# xuefei-lab7.net
KiCad netlist of a schematic drawn in EAGLE
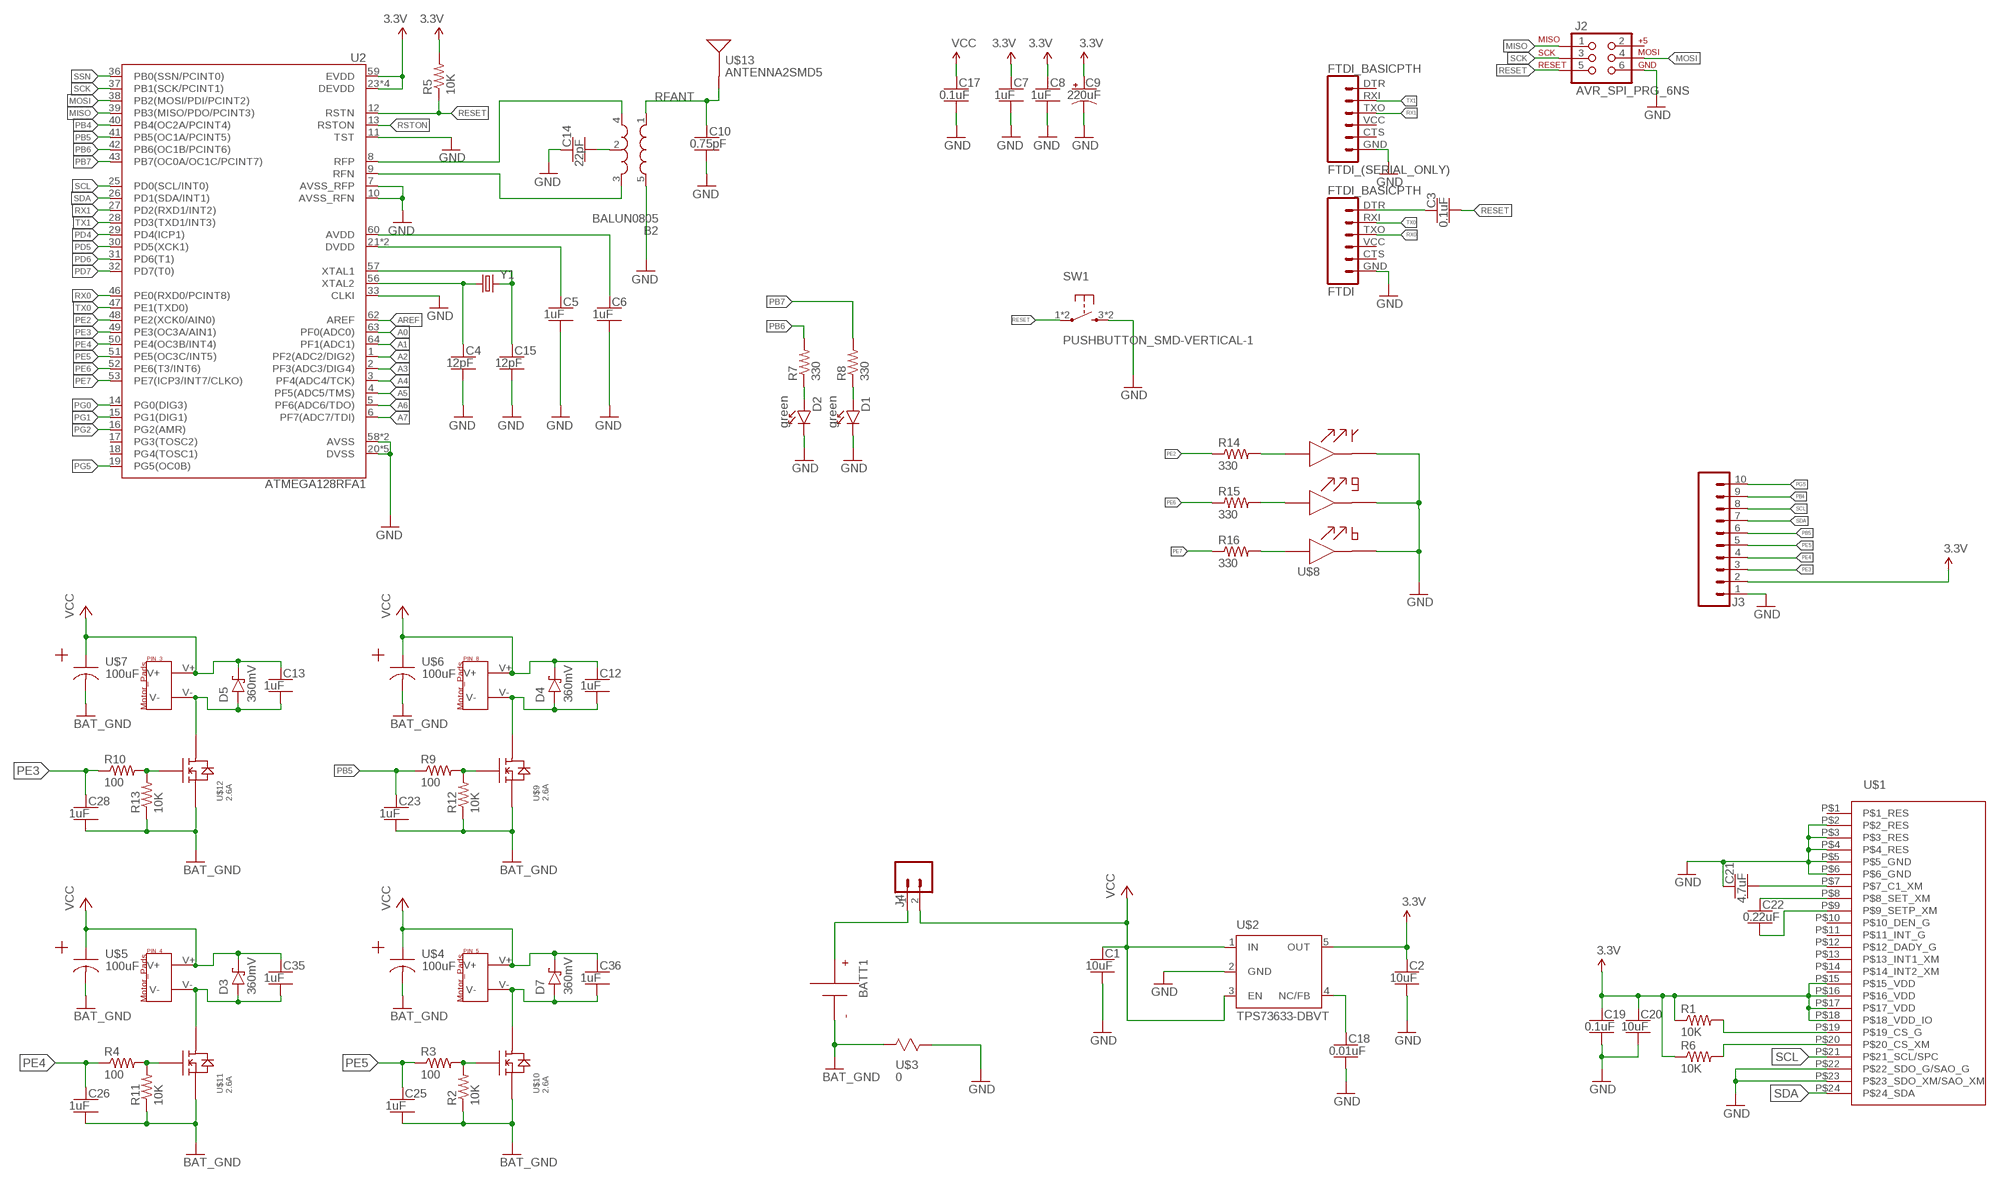
[diagram p0: schematic, sheet 1]

(export (version "E")
  (design (tool "Eeschema 10.0.6"))
  (components
    (comp (ref "B2")
      (value "BALUN0805")
      (footprint "eagle-import:BALUN")
      (fields (field (name "MFR") "Wurth Electronics Inc") (field (name "MPN") "748421245"))
      (libsource (lib "eagle-import") (part "BALUN0805"))
    )
    (comp (ref "BATT1")
      (value "BATTERY-HUBSAN-W/HOLDER")
      (footprint "eagle-import:BATTERY-W_HOLDER-380MAH-HUBSAN")
      (fields
        (field (name "MFR") "HUBSAN")
        (field (name "MPN") "X4-H107C-8-in-1")
        (field (name "CREATOR") "Swanson")
      )
      (libsource (lib "eagle-import") (part "BATTERY-HUBSAN-W/HOLDER"))
    )
    (comp (ref "C1")
      (value "10uF")
      (footprint "eagle-import:CAPC2012X140_HS")
      (fields
        (field (name "MFR") "Murata Electronics North America")
        (field (name "MPN") "GRM21BR61E106KA73L")
      )
      (libsource (lib "eagle-import") (part "CAPACITOR-NP_SMD-2012-0805_CERAMIC-10UF"))
    )
    (comp (ref "C2")
      (value "10uF")
      (footprint "eagle-import:CAPC2012X140_HS")
      (fields
        (field (name "MFR") "Murata Electronics North America")
        (field (name "MPN") "GRM21BR61E106KA73L")
      )
      (libsource (lib "eagle-import") (part "CAPACITOR-NP_SMD-2012-0805_CERAMIC-10UF"))
    )
    (comp (ref "C3")
      (value "0.1uF")
      (footprint "eagle-import:CAPC2012X140_HS")
      (fields
        (field (name "MFR") "Murata Electronics North America")
        (field (name "MPN") "GRM21BR71H104KA01L")
      )
      (libsource (lib "eagle-import") (part "CAPACITOR-NP_SMD-2012-0805_CERAMIC-0.1UF"))
    )
    (comp (ref "C4")
      (value "12pF")
      (footprint "eagle-import:CAPC2012X140_HS")
      (fields
        (field (name "MFR") "Murata Electronics North America")
        (field (name "MPN") "GRM21A5C2E120JW01D")
      )
      (libsource (lib "eagle-import") (part "CAPACITOR-NP_SMD-2012-0805_CERAMIC-12PF"))
    )
    (comp (ref "C5")
      (value "1uF")
      (footprint "eagle-import:CAPC2012X140_HS")
      (fields
        (field (name "MFR") "Murata Electronics North America")
        (field (name "MPN") "GRM21BR71H105KA12L")
      )
      (libsource (lib "eagle-import") (part "CAPACITOR-NP_SMD-2012-0805_CERAMIC-1UF"))
    )
    (comp (ref "C6")
      (value "1uF")
      (footprint "eagle-import:CAPC2012X140_HS")
      (fields
        (field (name "MFR") "Murata Electronics North America")
        (field (name "MPN") "GRM21BR71H105KA12L")
      )
      (libsource (lib "eagle-import") (part "CAPACITOR-NP_SMD-2012-0805_CERAMIC-1UF"))
    )
    (comp (ref "C7")
      (value "1uF")
      (footprint "eagle-import:CAPC2012X140_HS")
      (fields
        (field (name "MFR") "Murata Electronics North America")
        (field (name "MPN") "GRM21BR71H105KA12L")
      )
      (libsource (lib "eagle-import") (part "CAPACITOR-NP_SMD-2012-0805_CERAMIC-1UF"))
    )
    (comp (ref "C8")
      (value "1uF")
      (footprint "eagle-import:CAPC2012X140_HS")
      (fields
        (field (name "MFR") "Murata Electronics North America")
        (field (name "MPN") "GRM21BR71H105KA12L")
      )
      (libsource (lib "eagle-import") (part "CAPACITOR-NP_SMD-2012-0805_CERAMIC-1UF"))
    )
    (comp (ref "C9")
      (value "220uF")
      (footprint "eagle-import:CAPMP7343X310_HS")
      (fields (field (name "MFR") "AVX Corporation") (field (name "MPN") "TAJD227K006RNJ"))
      (libsource (lib "eagle-import") (part "CAPACITOR-POL_SMD-7043-D_TANTALUM-220UF"))
    )
    (comp (ref "C10")
      (value "0.75pF")
      (footprint "eagle-import:CAPC2012X140_HS")
      (fields
        (field (name "MFR") "Murata Electronics North America")
        (field (name "MPN") "GQM2195C2AR75CB01D")
      )
      (libsource (lib "eagle-import") (part "CAPACITOR-NP_SMD-2012-0805_CERAMIC-0.75PF"))
    )
    (comp (ref "C12")
      (value "1uF")
      (footprint "eagle-import:CAPC2012X140_HS")
      (fields
        (field (name "MFR") "Murata Electronics North America")
        (field (name "MPN") "GRM21BR71H105KA12L")
      )
      (libsource (lib "eagle-import") (part "CAPACITOR-NP_SMD-2012-0805_CERAMIC-1UF"))
    )
    (comp (ref "C13")
      (value "1uF")
      (footprint "eagle-import:CAPC2012X140_HS")
      (fields
        (field (name "MFR") "Murata Electronics North America")
        (field (name "MPN") "GRM21BR71H105KA12L")
      )
      (libsource (lib "eagle-import") (part "CAPACITOR-NP_SMD-2012-0805_CERAMIC-1UF"))
    )
    (comp (ref "C14")
      (value "22pF")
      (footprint "eagle-import:CAPC2012X140_HS")
      (fields
        (field (name "MFR") "Murata Electronics North America")
        (field (name "MPN") "GRM21A5C2E220JW01D")
      )
      (libsource (lib "eagle-import") (part "CAPACITOR-NP_SMD-2012-0805_CERAMIC-22PF"))
    )
    (comp (ref "C15")
      (value "12pF")
      (footprint "eagle-import:CAPC2012X140_HS")
      (fields
        (field (name "MFR") "Murata Electronics North America")
        (field (name "MPN") "GRM21A5C2E120JW01D")
      )
      (libsource (lib "eagle-import") (part "CAPACITOR-NP_SMD-2012-0805_CERAMIC-12PF"))
    )
    (comp (ref "C17")
      (value "0.1uF")
      (footprint "eagle-import:CAPC2012X140_HS")
      (fields
        (field (name "MFR") "Murata Electronics North America")
        (field (name "MPN") "GRM21BR71H104KA01L")
      )
      (libsource (lib "eagle-import") (part "CAPACITOR-NP_SMD-2012-0805_CERAMIC-0.1UF"))
    )
    (comp (ref "C18")
      (value "0.01uF")
      (footprint "eagle-import:CAPC2012X140_HS")
      (fields
        (field (name "MFR") "Murata Electronics North America")
        (field (name "MPN") "GRM2195C1H103FA01D")
      )
      (libsource (lib "eagle-import") (part "CAPACITOR-NP_SMD-2012-0805_CERAMIC-0.01UF"))
    )
    (comp (ref "C19")
      (value "0.1uF")
      (footprint "eagle-import:CAPC2012X140_HS")
      (fields
        (field (name "MFR") "Murata Electronics North America")
        (field (name "MPN") "GRM21BR71H104KA01L")
      )
      (libsource (lib "eagle-import") (part "CAPACITOR-NP_SMD-2012-0805_CERAMIC-0.1UF"))
    )
    (comp (ref "C20")
      (value "10uF")
      (footprint "eagle-import:CAPC2012X140_HS")
      (fields
        (field (name "MFR") "Murata Electronics North America")
        (field (name "MPN") "GRM21BR61E106KA73L")
      )
      (libsource (lib "eagle-import") (part "CAPACITOR-NP_SMD-2012-0805_CERAMIC-10UF"))
    )
    (comp (ref "C21")
      (value "4.7uF")
      (footprint "eagle-import:CAPC2012X140_HS")
      (fields
        (field (name "MFR") "Murata Electronics North America")
        (field (name "MPN") "GRM21BR61E475KA12L")
      )
      (libsource (lib "eagle-import") (part "CAPACITOR-NP_SMD-2012-0805_CERAMIC-4.7UF"))
    )
    (comp (ref "C22")
      (value "0.22uF")
      (footprint "eagle-import:CAPC2012X140_HS")
      (fields
        (field (name "MFR") "Murata Electronics North America")
        (field (name "MPN") "GRM21BR71H224KA01L")
      )
      (libsource (lib "eagle-import") (part "CAPACITOR-NP_SMD-2012-0805_CERAMIC-0.22UF"))
    )
    (comp (ref "C23")
      (value "1uF")
      (footprint "eagle-import:CAPC2012X140_HS")
      (fields
        (field (name "MFR") "Murata Electronics North America")
        (field (name "MPN") "GRM21BR71H105KA12L")
      )
      (libsource (lib "eagle-import") (part "CAPACITOR-NP_SMD-2012-0805_CERAMIC-1UF"))
    )
    (comp (ref "C25")
      (value "1uF")
      (footprint "eagle-import:CAPC2012X140_HS")
      (fields
        (field (name "MFR") "Murata Electronics North America")
        (field (name "MPN") "GRM21BR71H105KA12L")
      )
      (libsource (lib "eagle-import") (part "CAPACITOR-NP_SMD-2012-0805_CERAMIC-1UF"))
    )
    (comp (ref "C26")
      (value "1uF")
      (footprint "eagle-import:CAPC2012X140_HS")
      (fields
        (field (name "MFR") "Murata Electronics North America")
        (field (name "MPN") "GRM21BR71H105KA12L")
      )
      (libsource (lib "eagle-import") (part "CAPACITOR-NP_SMD-2012-0805_CERAMIC-1UF"))
    )
    (comp (ref "C28")
      (value "1uF")
      (footprint "eagle-import:CAPC2012X140_HS")
      (fields
        (field (name "MFR") "Murata Electronics North America")
        (field (name "MPN") "GRM21BR71H105KA12L")
      )
      (libsource (lib "eagle-import") (part "CAPACITOR-NP_SMD-2012-0805_CERAMIC-1UF"))
    )
    (comp (ref "C35")
      (value "1uF")
      (footprint "eagle-import:CAPC2012X140_HS")
      (fields
        (field (name "MFR") "Murata Electronics North America")
        (field (name "MPN") "GRM21BR71H105KA12L")
      )
      (libsource (lib "eagle-import") (part "CAPACITOR-NP_SMD-2012-0805_CERAMIC-1UF"))
    )
    (comp (ref "C36")
      (value "1uF")
      (footprint "eagle-import:CAPC2012X140_HS")
      (fields
        (field (name "MFR") "Murata Electronics North America")
        (field (name "MPN") "GRM21BR71H105KA12L")
      )
      (libsource (lib "eagle-import") (part "CAPACITOR-NP_SMD-2012-0805_CERAMIC-1UF"))
    )
    (comp (ref "D1")
      (value "green")
      (footprint "eagle-import:LEDSC125X200X120-2_HS")
      (fields (field (name "MFR") "Lite-On Inc") (field (name "MPN") "LTST-C170GKT"))
      (libsource (lib "eagle-import") (part "DIODE-LED_SMD-2012-0805-GREEN"))
    )
    (comp (ref "D2")
      (value "green")
      (footprint "eagle-import:LEDSC125X200X120-2_HS")
      (fields (field (name "MFR") "Lite-On Inc") (field (name "MPN") "LTST-C170GKT"))
      (libsource (lib "eagle-import") (part "DIODE-LED_SMD-2012-0805-GREEN"))
    )
    (comp (ref "D3")
      (value "360mV")
      (footprint "eagle-import:SOD3716X135_HS")
      (fields
        (field (name "MFR") "Toshiba Semiconductor and Storage")
        (field (name "MPN") "CRS08(TE85L,Q,M)")
      )
      (libsource (lib "eagle-import") (part "DIODE-SCHOTTKY_SMD-SOD123-360MV"))
    )
    (comp (ref "D4")
      (value "360mV")
      (footprint "eagle-import:SOD3716X135_HS")
      (fields
        (field (name "MFR") "Toshiba Semiconductor and Storage")
        (field (name "MPN") "CRS08(TE85L,Q,M)")
      )
      (libsource (lib "eagle-import") (part "DIODE-SCHOTTKY_SMD-SOD123-360MV"))
    )
    (comp (ref "D5")
      (value "360mV")
      (footprint "eagle-import:SOD3716X135_HS")
      (fields
        (field (name "MFR") "Toshiba Semiconductor and Storage")
        (field (name "MPN") "CRS08(TE85L,Q,M)")
      )
      (libsource (lib "eagle-import") (part "DIODE-SCHOTTKY_SMD-SOD123-360MV"))
    )
    (comp (ref "D7")
      (value "360mV")
      (footprint "eagle-import:SOD3716X135_HS")
      (fields
        (field (name "MFR") "Toshiba Semiconductor and Storage")
        (field (name "MPN") "CRS08(TE85L,Q,M)")
      )
      (libsource (lib "eagle-import") (part "DIODE-SCHOTTKY_SMD-SOD123-360MV"))
    )
    (comp (ref "FTDI")
      (value "FTDI_BASICPTH")
      (footprint "eagle-import:FTDI_BASIC")
      (fields (field (name "MFR") "Amphenol FCI") (field (name "MPN") "68016-406HLF"))
      (libsource (lib "eagle-import") (part "FTDI_BASICPTH"))
    )
    (comp (ref "FTDI_(SERIAL_ONLY)")
      (value "FTDI_BASICPTH")
      (footprint "eagle-import:FTDI_BASIC")
      (fields (field (name "MFR") "Amphenol FCI") (field (name "MPN") "68016-406HLF"))
      (libsource (lib "eagle-import") (part "FTDI_BASICPTH"))
    )
    (comp (ref "J2")
      (value "AVR_SPI_PRG_6NS")
      (footprint "eagle-import:2X3-NS")
      (fields (field (name "MFR") "Amphenol FCI") (field (name "MPN") "67997-206HLF"))
      (libsource (lib "eagle-import") (part "AVR_SPI_PRG_6NS"))
    )
    (comp (ref "J3")
      (value "SIP-10_TH-254X10-1")
      (footprint "eagle-import:HDRV10W63P254_10X1_2540X254H838_HS")
      (fields (field (name "MFR") "Amphenol FCI") (field (name "MPN") "68000-110HLF"))
      (libsource (lib "eagle-import") (part "SIP-10_TH-254X10-1"))
    )
    (comp (ref "J4")
      (value "MALE_HEADER_2POS-2X1-0.1IN")
      (footprint "eagle-import:MALE_HEADER_2X1_0.1IN")
      (fields
        (field (name "MFR") "3M")
        (field (name "MPN") "961102-6404-AR")
        (field (name "CREATOR") "SWANSON")
      )
      (libsource (lib "eagle-import") (part "MALE_HEADER_2POS-2X1-0.1IN"))
    )
    (comp (ref "PIN_3")
      (value "MOTOR_PADS")
      (footprint "eagle-import:MOTOR_PADS")
      (fields (field (name "MFR") "NA"))
      (libsource (lib "eagle-import") (part "MOTOR_PADS"))
    )
    (comp (ref "PIN_4")
      (value "MOTOR_PADS")
      (footprint "eagle-import:MOTOR_PADS")
      (fields (field (name "MFR") "NA"))
      (libsource (lib "eagle-import") (part "MOTOR_PADS"))
    )
    (comp (ref "PIN_5")
      (value "MOTOR_PADS")
      (footprint "eagle-import:MOTOR_PADS")
      (fields (field (name "MFR") "NA"))
      (libsource (lib "eagle-import") (part "MOTOR_PADS"))
    )
    (comp (ref "PIN_8")
      (value "MOTOR_PADS")
      (footprint "eagle-import:MOTOR_PADS")
      (fields (field (name "MFR") "NA"))
      (libsource (lib "eagle-import") (part "MOTOR_PADS"))
    )
    (comp (ref "R1")
      (value "10K")
      (footprint "eagle-import:RESC2012X60_HS")
      (fields (field (name "MFR") "Yageo") (field (name "MPN") "RC0805JR-0710KL"))
      (libsource (lib "eagle-import") (part "RESISTOR_SMD-2012-0805-10K"))
    )
    (comp (ref "R2")
      (value "10K")
      (footprint "eagle-import:RESC2012X60_HS")
      (fields (field (name "MFR") "Yageo") (field (name "MPN") "RC0805JR-0710KL"))
      (libsource (lib "eagle-import") (part "RESISTOR_SMD-2012-0805-10K"))
    )
    (comp (ref "R3")
      (value "100")
      (footprint "eagle-import:RESC2012X60_HS")
      (fields (field (name "MFR") "Yageo") (field (name "MPN") "RC0805JR-07100RL"))
      (libsource (lib "eagle-import") (part "RESISTOR_SMD-2012-0805-100"))
    )
    (comp (ref "R4")
      (value "100")
      (footprint "eagle-import:RESC2012X60_HS")
      (fields (field (name "MFR") "Yageo") (field (name "MPN") "RC0805JR-07100RL"))
      (libsource (lib "eagle-import") (part "RESISTOR_SMD-2012-0805-100"))
    )
    (comp (ref "R5")
      (value "10K")
      (footprint "eagle-import:RESC2012X60_HS")
      (fields (field (name "MFR") "Yageo") (field (name "MPN") "RC0805JR-0710KL"))
      (libsource (lib "eagle-import") (part "RESISTOR_SMD-2012-0805-10K"))
    )
    (comp (ref "R6")
      (value "10K")
      (footprint "eagle-import:RESC2012X60_HS")
      (fields (field (name "MFR") "Yageo") (field (name "MPN") "RC0805JR-0710KL"))
      (libsource (lib "eagle-import") (part "RESISTOR_SMD-2012-0805-10K"))
    )
    (comp (ref "R7")
      (value "330")
      (footprint "eagle-import:RESC2012X60_HS")
      (fields (field (name "MFR") "Yageo") (field (name "MPN") "RC0805JR-07330RL"))
      (libsource (lib "eagle-import") (part "RESISTOR_SMD-2012-0805-330"))
    )
    (comp (ref "R8")
      (value "330")
      (footprint "eagle-import:RESC2012X60_HS")
      (fields (field (name "MFR") "Yageo") (field (name "MPN") "RC0805JR-07330RL"))
      (libsource (lib "eagle-import") (part "RESISTOR_SMD-2012-0805-330"))
    )
    (comp (ref "R9")
      (value "100")
      (footprint "eagle-import:RESC2012X60_HS")
      (fields (field (name "MFR") "Yageo") (field (name "MPN") "RC0805JR-07100RL"))
      (libsource (lib "eagle-import") (part "RESISTOR_SMD-2012-0805-100"))
    )
    (comp (ref "R10")
      (value "100")
      (footprint "eagle-import:RESC2012X60_HS")
      (fields (field (name "MFR") "Yageo") (field (name "MPN") "RC0805JR-07100RL"))
      (libsource (lib "eagle-import") (part "RESISTOR_SMD-2012-0805-100"))
    )
    (comp (ref "R11")
      (value "10K")
      (footprint "eagle-import:RESC2012X60_HS")
      (fields (field (name "MFR") "Yageo") (field (name "MPN") "RC0805JR-0710KL"))
      (libsource (lib "eagle-import") (part "RESISTOR_SMD-2012-0805-10K"))
    )
    (comp (ref "R12")
      (value "10K")
      (footprint "eagle-import:RESC2012X60_HS")
      (fields (field (name "MFR") "Yageo") (field (name "MPN") "RC0805JR-0710KL"))
      (libsource (lib "eagle-import") (part "RESISTOR_SMD-2012-0805-10K"))
    )
    (comp (ref "R13")
      (value "10K")
      (footprint "eagle-import:RESC2012X60_HS")
      (fields (field (name "MFR") "Yageo") (field (name "MPN") "RC0805JR-0710KL"))
      (libsource (lib "eagle-import") (part "RESISTOR_SMD-2012-0805-10K"))
    )
    (comp (ref "R14")
      (value "330")
      (footprint "eagle-import:RESC2012X60_HS")
      (fields (field (name "MFR") "Yageo") (field (name "MPN") "RC0805JR-07330RL"))
      (libsource (lib "eagle-import") (part "RESISTOR_SMD-2012-0805-330"))
    )
    (comp (ref "R15")
      (value "330")
      (footprint "eagle-import:RESC2012X60_HS")
      (fields (field (name "MFR") "Yageo") (field (name "MPN") "RC0805JR-07330RL"))
      (libsource (lib "eagle-import") (part "RESISTOR_SMD-2012-0805-330"))
    )
    (comp (ref "R16")
      (value "330")
      (footprint "eagle-import:RESC2012X60_HS")
      (fields (field (name "MFR") "Yageo") (field (name "MPN") "RC0805JR-07330RL"))
      (libsource (lib "eagle-import") (part "RESISTOR_SMD-2012-0805-330"))
    )
    (comp (ref "SW1")
      (value "PUSHBUTTON_SMD-VERTICAL-1")
      (footprint "eagle-import:TE_FSM8JSMA_HS")
      (fields (field (name "MFR") "TE Connectivity Alcoswitch Switches") (field (name "MPN") "FSM4JSMA"))
      (libsource (lib "eagle-import") (part "PUSHBUTTON_SMD-VERTICAL-1"))
    )
    (comp (ref "U$1")
      (value "IMU")
      (footprint "eagle-import:LGA-24_4X4MM")
      (fields
        (field (name "MFR") "STMicroelectronics")
        (field (name "MPN") "LSM9DS0TR")
        (field (name "CREATOR") "Xuefei")
      )
      (libsource (lib "eagle-import") (part "IMU"))
    )
    (comp (ref "U$2")
      (value "TPS73633-DBVT")
      (footprint "eagle-import:SOT23-DBV")
      (fields (field (name "MFR") "Texas Instruments") (field (name "MPN") "LP3985IM5X-3.0/NOPB"))
      (libsource (lib "eagle-import") (part "TPS73633-DBVT"))
    )
    (comp (ref "U$3")
      (value "0")
      (footprint "eagle-import:SMD_RESISTOR")
      (fields
        (field (name "MFR") "Yageo")
        (field (name "MPN") "RC0805JR-070RL")
        (field (name "CREATOR") "Xuefei")
      )
      (libsource (lib "eagle-import") (part "RESISTOR"))
    )
    (comp (ref "U$4")
      (value "100uF")
      (footprint "eagle-import:TAJB_SMB_POLAR_CAP")
      (fields
        (field (name "MFR") "AVX Corporation")
        (field (name "MPN") "TAJB107K006RNJ")
        (field (name "CREATOR") "Xuefei")
      )
      (libsource (lib "eagle-import") (part "POLAR_CAP"))
    )
    (comp (ref "U$5")
      (value "100uF")
      (footprint "eagle-import:TAJB_SMB_POLAR_CAP")
      (fields
        (field (name "MFR") "AVX Corporation")
        (field (name "MPN") "TAJB107K006RNJ")
        (field (name "CREATOR") "Xuefei")
      )
      (libsource (lib "eagle-import") (part "POLAR_CAP"))
    )
    (comp (ref "U$6")
      (value "100uF")
      (footprint "eagle-import:TAJB_SMB_POLAR_CAP")
      (fields
        (field (name "MFR") "AVX Corporation")
        (field (name "MPN") "TAJB107K006RNJ")
        (field (name "CREATOR") "Xuefei")
      )
      (libsource (lib "eagle-import") (part "POLAR_CAP"))
    )
    (comp (ref "U$7")
      (value "100uF")
      (footprint "eagle-import:TAJB_SMB_POLAR_CAP")
      (fields
        (field (name "MFR") "AVX Corporation")
        (field (name "MPN") "TAJB107K006RNJ")
        (field (name "CREATOR") "Xuefei")
      )
      (libsource (lib "eagle-import") (part "POLAR_CAP"))
    )
    (comp (ref "U$8")
      (value "QBLP679E-RGB")
      (footprint "eagle-import:QBLP679E-RGB")
      (fields (field (name "MFR") "QT Brightek (QTB)") (field (name "CREATOR") "Xuefei"))
      (libsource (lib "eagle-import") (part "QBLP679E-RGB"))
    )
    (comp (ref "U$9")
      (value "2.6A")
      (footprint "eagle-import:LITTLE_FOOT_MOSFET_W__HEAT_SPREADER")
      (fields
        (field (name "MFR") "Vishay Siliconix")
        (field (name "MPN") "SI2302CDS-T1-E3")
        (field (name "CREATOR") "Xuefei")
      )
      (libsource (lib "eagle-import") (part "N-CHANNEL_MOSFETW/_HEAT_SINK"))
    )
    (comp (ref "U$10")
      (value "2.6A")
      (footprint "eagle-import:LITTLE_FOOT_MOSFET_W__HEAT_SPREADER")
      (fields
        (field (name "MFR") "Vishay Siliconix")
        (field (name "MPN") "SI2302CDS-T1-E3")
        (field (name "CREATOR") "Xuefei")
      )
      (libsource (lib "eagle-import") (part "N-CHANNEL_MOSFETW/_HEAT_SINK"))
    )
    (comp (ref "U$11")
      (value "2.6A")
      (footprint "eagle-import:LITTLE_FOOT_MOSFET_W__HEAT_SPREADER")
      (fields
        (field (name "MFR") "Vishay Siliconix")
        (field (name "MPN") "SI2302CDS-T1-E3")
        (field (name "CREATOR") "Xuefei")
      )
      (libsource (lib "eagle-import") (part "N-CHANNEL_MOSFETW/_HEAT_SINK"))
    )
    (comp (ref "U$12")
      (value "2.6A")
      (footprint "eagle-import:LITTLE_FOOT_MOSFET_W__HEAT_SPREADER")
      (fields
        (field (name "MFR") "Vishay Siliconix")
        (field (name "MPN") "SI2302CDS-T1-E3")
        (field (name "CREATOR") "Xuefei")
      )
      (libsource (lib "eagle-import") (part "N-CHANNEL_MOSFETW/_HEAT_SINK"))
    )
    (comp (ref "U$13")
      (value "ANTENNA2SMD5")
      (footprint "eagle-import:ANTENNA-CHIP5")
      (fields (field (name "MFR") "Linx Technologies Inc.") (field (name "MPN") "ANT-2.45-CHP-T"))
      (libsource (lib "eagle-import") (part "ANTENNA2SMD5"))
    )
    (comp (ref "U2")
      (value "ATMEGA128RFA1")
      (footprint "eagle-import:QFN-64")
      (fields (field (name "MFR") "Atmel") (field (name "MPN") "ATMEGA128RFA1-ZUR00"))
      (libsource (lib "eagle-import") (part "ATMEGA128RFA1"))
    )
    (comp (ref "Y1")
      (value "CRYSTAL5X3")
      (footprint "eagle-import:CRYSTAL-SMD-5X3")
      (fields (field (name "MFR") "Abracon LLC") (field (name "MPN") "ABM3B-16.000MHZ-B2-T"))
      (libsource (lib "eagle-import") (part "CRYSTAL5X3"))
    )
  )
  (nets
    (net (code "1") (name "/RFANT") (class "Default")
      (node (ref "B2") (pin "1") (pinfunction "IN_1") (pintype "bidirectional"))
      (node (ref "C10") (pin "1") (pinfunction "1_1") (pintype "passive"))
      (node (ref "U$13") (pin "FEED") (pinfunction "SIGNAL_FEED") (pintype "bidirectional"))
    )
    (net (code "2") (name "3.3V") (class "Default")
      (node (ref "C19") (pin "1") (pinfunction "1_1") (pintype "passive"))
      (node (ref "C2") (pin "1") (pinfunction "1_1") (pintype "passive"))
      (node (ref "C20") (pin "1") (pinfunction "1_1") (pintype "passive"))
      (node (ref "C7") (pin "1") (pinfunction "1_1") (pintype "passive"))
      (node (ref "C8") (pin "1") (pinfunction "1_1") (pintype "passive"))
      (node (ref "C9") (pin "1") (pinfunction "+_1") (pintype "passive"))
      (node (ref "J3") (pin "2") (pinfunction "2_2") (pintype "passive"))
      (node (ref "R1") (pin "1") (pinfunction "1_1") (pintype "passive"))
      (node (ref "R5") (pin "2") (pinfunction "2_2") (pintype "passive"))
      (node (ref "R6") (pin "1") (pinfunction "1_1") (pintype "passive"))
      (node (ref "U$1") (pin "P$15") (pinfunction "P$15_VDD_P$15") (pintype "bidirectional"))
      (node (ref "U$1") (pin "P$16") (pinfunction "P$16_VDD_P$16") (pintype "bidirectional"))
      (node (ref "U$1") (pin "P$17") (pinfunction "P$17_VDD_P$17") (pintype "bidirectional"))
      (node (ref "U$1") (pin "P$18") (pinfunction "P$18_VDD_IO_P$18") (pintype "bidirectional"))
      (node (ref "U$2") (pin "5") (pinfunction "OUT_5") (pintype "passive"))
      (node (ref "U2") (pin "23") (pinfunction "DEVDD_23") (pintype "bidirectional"))
      (node (ref "U2") (pin "34") (pinfunction "DEVDD_34") (pintype "bidirectional"))
      (node (ref "U2") (pin "44") (pinfunction "DEVDD_44") (pintype "bidirectional"))
      (node (ref "U2") (pin "54") (pinfunction "DEVDD_54") (pintype "bidirectional"))
      (node (ref "U2") (pin "59") (pinfunction "EVDD_59") (pintype "bidirectional"))
    )
    (net (code "3") (name "A0") (class "Default")
      (node (ref "U2") (pin "63") (pinfunction "PF0(ADC0)_63") (pintype "bidirectional"))
    )
    (net (code "4") (name "A1") (class "Default")
      (node (ref "U2") (pin "64") (pinfunction "PF1(ADC1)_64") (pintype "bidirectional"))
    )
    (net (code "5") (name "A2") (class "Default")
      (node (ref "U2") (pin "1") (pinfunction "PF2(ADC2/DIG2)_1") (pintype "bidirectional"))
    )
    (net (code "6") (name "A3") (class "Default")
      (node (ref "U2") (pin "2") (pinfunction "PF3(ADC3/DIG4)_2") (pintype "bidirectional"))
    )
    (net (code "7") (name "A4") (class "Default")
      (node (ref "U2") (pin "3") (pinfunction "PF4(ADC4/TCK)_3") (pintype "bidirectional"))
    )
    (net (code "8") (name "A5") (class "Default")
      (node (ref "U2") (pin "4") (pinfunction "PF5(ADC5/TMS)_4") (pintype "bidirectional"))
    )
    (net (code "9") (name "A6") (class "Default")
      (node (ref "U2") (pin "5") (pinfunction "PF6(ADC6/TDO)_5") (pintype "bidirectional"))
    )
    (net (code "10") (name "A7") (class "Default")
      (node (ref "U2") (pin "6") (pinfunction "PF7(ADC7/TDI)_6") (pintype "bidirectional"))
    )
    (net (code "11") (name "AREF") (class "Default")
      (node (ref "U2") (pin "62") (pinfunction "AREF_62") (pintype "bidirectional"))
    )
    (net (code "12") (name "BAT_GND") (class "Default")
      (node (ref "BATT1") (pin "-") (pinfunction "N_-") (pintype "bidirectional"))
      (node (ref "C23") (pin "2") (pinfunction "2_2") (pintype "passive"))
      (node (ref "C25") (pin "2") (pinfunction "2_2") (pintype "passive"))
      (node (ref "C26") (pin "2") (pinfunction "2_2") (pintype "passive"))
      (node (ref "C28") (pin "2") (pinfunction "2_2") (pintype "passive"))
      (node (ref "R11") (pin "1") (pinfunction "1_1") (pintype "passive"))
      (node (ref "R12") (pin "1") (pinfunction "1_1") (pintype "passive"))
      (node (ref "R13") (pin "1") (pinfunction "1_1") (pintype "passive"))
      (node (ref "R2") (pin "1") (pinfunction "1_1") (pintype "passive"))
      (node (ref "U$10") (pin "P$2") (pinfunction "P$2_S_P$2") (pintype "bidirectional"))
      (node (ref "U$11") (pin "P$2") (pinfunction "P$2_S_P$2") (pintype "bidirectional"))
      (node (ref "U$12") (pin "P$2") (pinfunction "P$2_S_P$2") (pintype "bidirectional"))
      (node (ref "U$3") (pin "P$1") (pinfunction "P$1_P$1") (pintype "bidirectional"))
      (node (ref "U$4") (pin "P$2") (pinfunction "2_P$2") (pintype "passive"))
      (node (ref "U$5") (pin "P$2") (pinfunction "2_P$2") (pintype "passive"))
      (node (ref "U$6") (pin "P$2") (pinfunction "2_P$2") (pintype "passive"))
      (node (ref "U$7") (pin "P$2") (pinfunction "2_P$2") (pintype "passive"))
      (node (ref "U$9") (pin "P$2") (pinfunction "P$2_S_P$2") (pintype "bidirectional"))
    )
    (net (code "13") (name "GND") (class "Default")
      (node (ref "B2") (pin "5") (pinfunction "GND_5") (pintype "bidirectional"))
      (node (ref "C1") (pin "2") (pinfunction "2_2") (pintype "passive"))
      (node (ref "C10") (pin "2") (pinfunction "2_2") (pintype "passive"))
      (node (ref "C14") (pin "1") (pinfunction "1_1") (pintype "passive"))
      (node (ref "C15") (pin "2") (pinfunction "2_2") (pintype "passive"))
      (node (ref "C17") (pin "2") (pinfunction "2_2") (pintype "passive"))
      (node (ref "C18") (pin "2") (pinfunction "2_2") (pintype "passive"))
      (node (ref "C19") (pin "2") (pinfunction "2_2") (pintype "passive"))
      (node (ref "C2") (pin "2") (pinfunction "2_2") (pintype "passive"))
      (node (ref "C20") (pin "2") (pinfunction "2_2") (pintype "passive"))
      (node (ref "C21") (pin "1") (pinfunction "1_1") (pintype "passive"))
      (node (ref "C4") (pin "2") (pinfunction "2_2") (pintype "passive"))
      (node (ref "C5") (pin "2") (pinfunction "2_2") (pintype "passive"))
      (node (ref "C6") (pin "2") (pinfunction "2_2") (pintype "passive"))
      (node (ref "C7") (pin "2") (pinfunction "2_2") (pintype "passive"))
      (node (ref "C8") (pin "2") (pinfunction "2_2") (pintype "passive"))
      (node (ref "C9") (pin "2") (pinfunction "-_2") (pintype "passive"))
      (node (ref "D1") (pin "C") (pinfunction "C_C") (pintype "passive"))
      (node (ref "D2") (pin "C") (pinfunction "C_C") (pintype "passive"))
      (node (ref "FTDI") (pin "GND") (pinfunction "6_GND") (pintype "passive"))
      (node (ref "FTDI_(SERIAL_ONLY)") (pin "GND") (pinfunction "6_GND") (pintype "passive"))
      (node (ref "J2") (pin "6") (pinfunction "6_6") (pintype "passive"))
      (node (ref "J3") (pin "1") (pinfunction "1_1") (pintype "passive"))
      (node (ref "SW1") (pin "3") (pinfunction "2_3") (pintype "passive"))
      (node (ref "SW1") (pin "4") (pinfunction "2_4") (pintype "passive"))
      (node (ref "U$1") (pin "P$2") (pinfunction "P$2_RES_P$2") (pintype "bidirectional"))
      (node (ref "U$1") (pin "P$22") (pinfunction "P$22_SDO_G/SAO_G_P$22") (pintype "bidirectional"))
      (node (ref "U$1") (pin "P$23") (pinfunction "P$23_SDO_XM/SAO_XM_P$23") (pintype "bidirectional"))
      (node (ref "U$1") (pin "P$3") (pinfunction "P$3_RES_P$3") (pintype "bidirectional"))
      (node (ref "U$1") (pin "P$4") (pinfunction "P$4_RES_P$4") (pintype "bidirectional"))
      (node (ref "U$1") (pin "P$5") (pinfunction "P$5_GND_P$5") (pintype "bidirectional"))
      (node (ref "U$1") (pin "P$6") (pinfunction "P$6_GND_P$6") (pintype "bidirectional"))
      (node (ref "U$2") (pin "2") (pinfunction "GND_2") (pintype "input"))
      (node (ref "U$3") (pin "P$2") (pinfunction "P$2_P$2") (pintype "bidirectional"))
      (node (ref "U$8") (pin "P$1") (pinfunction "P$1_P$1") (pintype "bidirectional"))
      (node (ref "U$8") (pin "P$2") (pinfunction "P$2_P$2") (pintype "bidirectional"))
      (node (ref "U$8") (pin "P$3") (pinfunction "P$3_P$3") (pintype "bidirectional"))
      (node (ref "U2") (pin "10") (pinfunction "AVSS_RFN_10") (pintype "bidirectional"))
      (node (ref "U2") (pin "11") (pinfunction "TST_11") (pintype "bidirectional"))
      (node (ref "U2") (pin "20") (pinfunction "DVSS_20") (pintype "bidirectional"))
      (node (ref "U2") (pin "24") (pinfunction "DVSS_24") (pintype "bidirectional"))
      (node (ref "U2") (pin "33") (pinfunction "CLKI_33") (pintype "bidirectional"))
      (node (ref "U2") (pin "35") (pinfunction "DVSS_35") (pintype "bidirectional"))
      (node (ref "U2") (pin "45") (pinfunction "DVSS_45") (pintype "bidirectional"))
      (node (ref "U2") (pin "55") (pinfunction "DVSS_55") (pintype "bidirectional"))
      (node (ref "U2") (pin "58") (pinfunction "AVSS_58") (pintype "bidirectional"))
      (node (ref "U2") (pin "61") (pinfunction "AVSS_61") (pintype "bidirectional"))
      (node (ref "U2") (pin "7") (pinfunction "AVSS_RFP_7") (pintype "bidirectional"))
    )
    (net (code "14") (name "MISO") (class "Default")
      (node (ref "J2") (pin "1") (pinfunction "1_1") (pintype "passive"))
      (node (ref "U2") (pin "39") (pinfunction "PB3(MISO/PDO/PCINT3)_39") (pintype "bidirectional"))
    )
    (net (code "15") (name "MOSI") (class "Default")
      (node (ref "J2") (pin "4") (pinfunction "4_4") (pintype "passive"))
      (node (ref "U2") (pin "38") (pinfunction "PB2(MOSI/PDI/PCINT2)_38") (pintype "bidirectional"))
    )
    (net (code "16") (name "Net-(B2-GND-Pad2)") (class "Default")
      (node (ref "B2") (pin "2") (pinfunction "GND_2") (pintype "bidirectional"))
      (node (ref "C14") (pin "2") (pinfunction "2_2") (pintype "passive"))
    )
    (net (code "17") (name "Net-(B2-OUT1)") (class "Default")
      (node (ref "B2") (pin "4") (pinfunction "OUT1_4") (pintype "bidirectional"))
      (node (ref "U2") (pin "8") (pinfunction "RFP_8") (pintype "bidirectional"))
    )
    (net (code "18") (name "Net-(B2-OUT2)") (class "Default")
      (node (ref "B2") (pin "3") (pinfunction "OUT2_3") (pintype "bidirectional"))
      (node (ref "U2") (pin "9") (pinfunction "RFN_9") (pintype "bidirectional"))
    )
    (net (code "19") (name "Net-(BATT1-P)") (class "Default")
      (node (ref "BATT1") (pin "+") (pinfunction "P_+") (pintype "bidirectional"))
      (node (ref "J4") (pin "1") (pinfunction "1_1") (pintype "passive"))
    )
    (net (code "20") (name "Net-(C5-Pad1)") (class "Default")
      (node (ref "C5") (pin "1") (pinfunction "1_1") (pintype "passive"))
      (node (ref "U2") (pin "21") (pinfunction "DVDD_21") (pintype "bidirectional"))
      (node (ref "U2") (pin "22") (pinfunction "DVDD_22") (pintype "bidirectional"))
    )
    (net (code "21") (name "Net-(D1-PadA)") (class "Default")
      (node (ref "D1") (pin "A") (pinfunction "A_A") (pintype "passive"))
      (node (ref "R8") (pin "1") (pinfunction "1_1") (pintype "passive"))
    )
    (net (code "22") (name "Net-(D2-PadA)") (class "Default")
      (node (ref "D2") (pin "A") (pinfunction "A_A") (pintype "passive"))
      (node (ref "R7") (pin "1") (pinfunction "1_1") (pintype "passive"))
    )
    (net (code "23") (name "Net-(FTDI-1)") (class "Default")
      (node (ref "C3") (pin "1") (pinfunction "1_1") (pintype "passive"))
      (node (ref "FTDI") (pin "DTR") (pinfunction "1_DTR") (pintype "passive"))
    )
    (net (code "24") (name "Net-(R14-Pad2)") (class "Default")
      (node (ref "R14") (pin "2") (pinfunction "2_2") (pintype "passive"))
      (node (ref "U$8") (pin "P$4") (pinfunction "P$4_P$4") (pintype "bidirectional"))
    )
    (net (code "25") (name "Net-(R15-Pad2)") (class "Default")
      (node (ref "R15") (pin "2") (pinfunction "2_2") (pintype "passive"))
      (node (ref "U$8") (pin "P$5") (pinfunction "P$5_P$5") (pintype "bidirectional"))
    )
    (net (code "26") (name "Net-(R16-Pad2)") (class "Default")
      (node (ref "R16") (pin "2") (pinfunction "2_2") (pintype "passive"))
      (node (ref "U$8") (pin "P$6") (pinfunction "P$6_P$6") (pintype "bidirectional"))
    )
    (net (code "27") (name "Net-(U$1-P$7_C1_XM)") (class "Default")
      (node (ref "C21") (pin "2") (pinfunction "2_2") (pintype "passive"))
      (node (ref "U$1") (pin "P$7") (pinfunction "P$7_C1_XM_P$7") (pintype "bidirectional"))
    )
    (net (code "28") (name "Net-(U$1-P$8_SET_XM)") (class "Default")
      (node (ref "C22") (pin "1") (pinfunction "1_1") (pintype "passive"))
      (node (ref "U$1") (pin "P$8") (pinfunction "P$8_SET_XM_P$8") (pintype "bidirectional"))
    )
    (net (code "29") (name "Net-(U$1-P$9_SETP_XM)") (class "Default")
      (node (ref "C22") (pin "2") (pinfunction "2_2") (pintype "passive"))
      (node (ref "U$1") (pin "P$9") (pinfunction "P$9_SETP_XM_P$9") (pintype "bidirectional"))
    )
    (net (code "30") (name "Net-(U$1-P$19_CS_G)") (class "Default")
      (node (ref "R1") (pin "2") (pinfunction "2_2") (pintype "passive"))
      (node (ref "U$1") (pin "P$19") (pinfunction "P$19_CS_G_P$19") (pintype "bidirectional"))
    )
    (net (code "31") (name "Net-(U$1-P$20_CS_XM)") (class "Default")
      (node (ref "R6") (pin "2") (pinfunction "2_2") (pintype "passive"))
      (node (ref "U$1") (pin "P$20") (pinfunction "P$20_CS_XM_P$20") (pintype "bidirectional"))
    )
    (net (code "32") (name "Net-(U$2-NC{slash}FB)") (class "Default")
      (node (ref "C18") (pin "1") (pinfunction "1_1") (pintype "passive"))
      (node (ref "U$2") (pin "4") (pinfunction "NC/FB_4") (pintype "passive"))
    )
    (net (code "33") (name "Net-(U$9-P$1_G)") (class "Default")
      (node (ref "R12") (pin "2") (pinfunction "2_2") (pintype "passive"))
      (node (ref "R9") (pin "2") (pinfunction "2_2") (pintype "passive"))
      (node (ref "U$9") (pin "P$1") (pinfunction "P$1_G_P$1") (pintype "bidirectional"))
    )
    (net (code "34") (name "Net-(U$9-P$3_D)") (class "Default")
      (node (ref "C12") (pin "2") (pinfunction "2_2") (pintype "passive"))
      (node (ref "D4") (pin "A") (pinfunction "A_A") (pintype "passive"))
      (node (ref "PIN_8") (pin "V-") (pinfunction "V-_V-") (pintype "bidirectional"))
      (node (ref "U$9") (pin "P$3") (pinfunction "P$3_D_P$3") (pintype "bidirectional"))
    )
    (net (code "35") (name "Net-(U$10-P$1_G)") (class "Default")
      (node (ref "R2") (pin "2") (pinfunction "2_2") (pintype "passive"))
      (node (ref "R3") (pin "2") (pinfunction "2_2") (pintype "passive"))
      (node (ref "U$10") (pin "P$1") (pinfunction "P$1_G_P$1") (pintype "bidirectional"))
    )
    (net (code "36") (name "Net-(U$10-P$3_D)") (class "Default")
      (node (ref "C36") (pin "2") (pinfunction "2_2") (pintype "passive"))
      (node (ref "D7") (pin "A") (pinfunction "A_A") (pintype "passive"))
      (node (ref "PIN_5") (pin "V-") (pinfunction "V-_V-") (pintype "bidirectional"))
      (node (ref "U$10") (pin "P$3") (pinfunction "P$3_D_P$3") (pintype "bidirectional"))
    )
    (net (code "37") (name "Net-(U$11-P$1_G)") (class "Default")
      (node (ref "R11") (pin "2") (pinfunction "2_2") (pintype "passive"))
      (node (ref "R4") (pin "2") (pinfunction "2_2") (pintype "passive"))
      (node (ref "U$11") (pin "P$1") (pinfunction "P$1_G_P$1") (pintype "bidirectional"))
    )
    (net (code "38") (name "Net-(U$11-P$3_D)") (class "Default")
      (node (ref "C35") (pin "2") (pinfunction "2_2") (pintype "passive"))
      (node (ref "D3") (pin "A") (pinfunction "A_A") (pintype "passive"))
      (node (ref "PIN_4") (pin "V-") (pinfunction "V-_V-") (pintype "bidirectional"))
      (node (ref "U$11") (pin "P$3") (pinfunction "P$3_D_P$3") (pintype "bidirectional"))
    )
    (net (code "39") (name "Net-(U$12-P$1_G)") (class "Default")
      (node (ref "R10") (pin "2") (pinfunction "2_2") (pintype "passive"))
      (node (ref "R13") (pin "2") (pinfunction "2_2") (pintype "passive"))
      (node (ref "U$12") (pin "P$1") (pinfunction "P$1_G_P$1") (pintype "bidirectional"))
    )
    (net (code "40") (name "Net-(U$12-P$3_D)") (class "Default")
      (node (ref "C13") (pin "2") (pinfunction "2_2") (pintype "passive"))
      (node (ref "D5") (pin "A") (pinfunction "A_A") (pintype "passive"))
      (node (ref "PIN_3") (pin "V-") (pinfunction "V-_V-") (pintype "bidirectional"))
      (node (ref "U$12") (pin "P$3") (pinfunction "P$3_D_P$3") (pintype "bidirectional"))
    )
    (net (code "41") (name "Net-(U2-AVDD)") (class "Default")
      (node (ref "C6") (pin "1") (pinfunction "1_1") (pintype "passive"))
      (node (ref "U2") (pin "60") (pinfunction "AVDD_60") (pintype "bidirectional"))
    )
    (net (code "42") (name "Net-(U2-XTAL1)") (class "Default")
      (node (ref "C15") (pin "1") (pinfunction "1_1") (pintype "passive"))
      (node (ref "U2") (pin "57") (pinfunction "XTAL1_57") (pintype "bidirectional"))
      (node (ref "Y1") (pin "3") (pinfunction "2_3") (pintype "passive"))
    )
    (net (code "43") (name "Net-(U2-XTAL2)") (class "Default")
      (node (ref "C4") (pin "1") (pinfunction "1_1") (pintype "passive"))
      (node (ref "U2") (pin "56") (pinfunction "XTAL2_56") (pintype "bidirectional"))
      (node (ref "Y1") (pin "1") (pinfunction "1_1") (pintype "passive"))
    )
    (net (code "44") (name "PB4") (class "Default")
      (node (ref "J3") (pin "9") (pinfunction "9_9") (pintype "passive"))
      (node (ref "U2") (pin "40") (pinfunction "PB4(OC2A/PCINT4)_40") (pintype "bidirectional"))
    )
    (net (code "45") (name "PB5") (class "Default")
      (node (ref "C23") (pin "1") (pinfunction "1_1") (pintype "passive"))
      (node (ref "J3") (pin "6") (pinfunction "6_6") (pintype "passive"))
      (node (ref "R9") (pin "1") (pinfunction "1_1") (pintype "passive"))
      (node (ref "U2") (pin "41") (pinfunction "PB5(OC1A/PCINT5)_41") (pintype "bidirectional"))
    )
    (net (code "46") (name "PB6") (class "Default")
      (node (ref "R7") (pin "2") (pinfunction "2_2") (pintype "passive"))
      (node (ref "U2") (pin "42") (pinfunction "PB6(OC1B/PCINT6)_42") (pintype "bidirectional"))
    )
    (net (code "47") (name "PB7") (class "Default")
      (node (ref "R8") (pin "2") (pinfunction "2_2") (pintype "passive"))
      (node (ref "U2") (pin "43") (pinfunction "PB7(OC0A/OC1C/PCINT7)_43") (pintype "bidirectional"))
    )
    (net (code "48") (name "PD4") (class "Default")
      (node (ref "U2") (pin "29") (pinfunction "PD4(ICP1)_29") (pintype "bidirectional"))
    )
    (net (code "49") (name "PD5") (class "Default")
      (node (ref "U2") (pin "30") (pinfunction "PD5(XCK1)_30") (pintype "bidirectional"))
    )
    (net (code "50") (name "PD6") (class "Default")
      (node (ref "U2") (pin "31") (pinfunction "PD6(T1)_31") (pintype "bidirectional"))
    )
    (net (code "51") (name "PD7") (class "Default")
      (node (ref "U2") (pin "32") (pinfunction "PD7(T0)_32") (pintype "bidirectional"))
    )
    (net (code "52") (name "PE2") (class "Default")
      (node (ref "R14") (pin "1") (pinfunction "1_1") (pintype "passive"))
      (node (ref "U2") (pin "48") (pinfunction "PE2(XCK0/AIN0)_48") (pintype "bidirectional"))
    )
    (net (code "53") (name "PE3") (class "Default")
      (node (ref "C28") (pin "1") (pinfunction "1_1") (pintype "passive"))
      (node (ref "J3") (pin "3") (pinfunction "3_3") (pintype "passive"))
      (node (ref "R10") (pin "1") (pinfunction "1_1") (pintype "passive"))
      (node (ref "U2") (pin "49") (pinfunction "PE3(OC3A/AIN1)_49") (pintype "bidirectional"))
    )
    (net (code "54") (name "PE4") (class "Default")
      (node (ref "C26") (pin "1") (pinfunction "1_1") (pintype "passive"))
      (node (ref "J3") (pin "4") (pinfunction "4_4") (pintype "passive"))
      (node (ref "R4") (pin "1") (pinfunction "1_1") (pintype "passive"))
      (node (ref "U2") (pin "50") (pinfunction "PE4(OC3B/INT4)_50") (pintype "bidirectional"))
    )
    (net (code "55") (name "PE5") (class "Default")
      (node (ref "C25") (pin "1") (pinfunction "1_1") (pintype "passive"))
      (node (ref "J3") (pin "5") (pinfunction "5_5") (pintype "passive"))
      (node (ref "R3") (pin "1") (pinfunction "1_1") (pintype "passive"))
      (node (ref "U2") (pin "51") (pinfunction "PE5(OC3C/INT5)_51") (pintype "bidirectional"))
    )
    (net (code "56") (name "PE6") (class "Default")
      (node (ref "R15") (pin "1") (pinfunction "1_1") (pintype "passive"))
      (node (ref "U2") (pin "52") (pinfunction "PE6(T3/INT6)_52") (pintype "bidirectional"))
    )
    (net (code "57") (name "PE7") (class "Default")
      (node (ref "R16") (pin "1") (pinfunction "1_1") (pintype "passive"))
      (node (ref "U2") (pin "53") (pinfunction "PE7(ICP3/INT7/CLKO)_53") (pintype "bidirectional"))
    )
    (net (code "58") (name "PG0") (class "Default")
      (node (ref "U2") (pin "14") (pinfunction "PG0(DIG3)_14") (pintype "bidirectional"))
    )
    (net (code "59") (name "PG1") (class "Default")
      (node (ref "U2") (pin "15") (pinfunction "PG1(DIG1)_15") (pintype "bidirectional"))
    )
    (net (code "60") (name "PG2") (class "Default")
      (node (ref "U2") (pin "16") (pinfunction "PG2(AMR)_16") (pintype "bidirectional"))
    )
    (net (code "61") (name "PG5") (class "Default")
      (node (ref "J3") (pin "10") (pinfunction "10_10") (pintype "passive"))
      (node (ref "U2") (pin "19") (pinfunction "PG5(OC0B)_19") (pintype "bidirectional"))
    )
    (net (code "62") (name "RESET") (class "Default")
      (node (ref "C3") (pin "2") (pinfunction "2_2") (pintype "passive"))
      (node (ref "J2") (pin "5") (pinfunction "5_5") (pintype "passive"))
      (node (ref "R5") (pin "1") (pinfunction "1_1") (pintype "passive"))
      (node (ref "SW1") (pin "1") (pinfunction "1_1") (pintype "passive"))
      (node (ref "SW1") (pin "2") (pinfunction "1_2") (pintype "passive"))
      (node (ref "U2") (pin "12") (pinfunction "RSTN_12") (pintype "bidirectional"))
    )
    (net (code "63") (name "RSTON") (class "Default")
      (node (ref "U2") (pin "13") (pinfunction "RSTON_13") (pintype "bidirectional"))
    )
    (net (code "64") (name "RX0") (class "Default")
      (node (ref "FTDI") (pin "TXO") (pinfunction "3_TXO") (pintype "passive"))
      (node (ref "U2") (pin "46") (pinfunction "PE0(RXD0/PCINT8)_46") (pintype "bidirectional"))
    )
    (net (code "65") (name "RX1") (class "Default")
      (node (ref "FTDI_(SERIAL_ONLY)") (pin "TXO") (pinfunction "3_TXO") (pintype "passive"))
      (node (ref "U2") (pin "27") (pinfunction "PD2(RXD1/INT2)_27") (pintype "bidirectional"))
    )
    (net (code "66") (name "SCK") (class "Default")
      (node (ref "J2") (pin "3") (pinfunction "3_3") (pintype "passive"))
      (node (ref "U2") (pin "37") (pinfunction "PB1(SCK/PCINT1)_37") (pintype "bidirectional"))
    )
    (net (code "67") (name "SCL") (class "Default")
      (node (ref "J3") (pin "8") (pinfunction "8_8") (pintype "passive"))
      (node (ref "U$1") (pin "P$21") (pinfunction "P$21_SCL/SPC_P$21") (pintype "bidirectional"))
      (node (ref "U2") (pin "25") (pinfunction "PD0(SCL/INT0)_25") (pintype "bidirectional"))
    )
    (net (code "68") (name "SDA") (class "Default")
      (node (ref "J3") (pin "7") (pinfunction "7_7") (pintype "passive"))
      (node (ref "U$1") (pin "P$24") (pinfunction "P$24_SDA_P$24") (pintype "bidirectional"))
      (node (ref "U2") (pin "26") (pinfunction "PD1(SDA/INT1)_26") (pintype "bidirectional"))
    )
    (net (code "69") (name "SSN") (class "Default")
      (node (ref "U2") (pin "36") (pinfunction "PB0(SSN/PCINT0)_36") (pintype "bidirectional"))
    )
    (net (code "70") (name "TX0") (class "Default")
      (node (ref "FTDI") (pin "RXI") (pinfunction "2_RXI") (pintype "passive"))
      (node (ref "U2") (pin "47") (pinfunction "PE1(TXD0)_47") (pintype "bidirectional"))
    )
    (net (code "71") (name "TX1") (class "Default")
      (node (ref "FTDI_(SERIAL_ONLY)") (pin "RXI") (pinfunction "2_RXI") (pintype "passive"))
      (node (ref "U2") (pin "28") (pinfunction "PD3(TXD1/INT3)_28") (pintype "bidirectional"))
    )
    (net (code "72") (name "VCC") (class "Default")
      (node (ref "C1") (pin "1") (pinfunction "1_1") (pintype "passive"))
      (node (ref "C12") (pin "1") (pinfunction "1_1") (pintype "passive"))
      (node (ref "C13") (pin "1") (pinfunction "1_1") (pintype "passive"))
      (node (ref "C17") (pin "1") (pinfunction "1_1") (pintype "passive"))
      (node (ref "C35") (pin "1") (pinfunction "1_1") (pintype "passive"))
      (node (ref "C36") (pin "1") (pinfunction "1_1") (pintype "passive"))
      (node (ref "D3") (pin "C") (pinfunction "C_C") (pintype "passive"))
      (node (ref "D4") (pin "C") (pinfunction "C_C") (pintype "passive"))
      (node (ref "D5") (pin "C") (pinfunction "C_C") (pintype "passive"))
      (node (ref "D7") (pin "C") (pinfunction "C_C") (pintype "passive"))
      (node (ref "J4") (pin "2") (pinfunction "2_2") (pintype "passive"))
      (node (ref "PIN_3") (pin "V+") (pinfunction "V+_V+") (pintype "bidirectional"))
      (node (ref "PIN_4") (pin "V+") (pinfunction "V+_V+") (pintype "bidirectional"))
      (node (ref "PIN_5") (pin "V+") (pinfunction "V+_V+") (pintype "bidirectional"))
      (node (ref "PIN_8") (pin "V+") (pinfunction "V+_V+") (pintype "bidirectional"))
      (node (ref "U$2") (pin "1") (pinfunction "IN_1") (pintype "input"))
      (node (ref "U$2") (pin "3") (pinfunction "EN_3") (pintype "input"))
      (node (ref "U$4") (pin "P$1") (pinfunction "1_P$1") (pintype "passive"))
      (node (ref "U$5") (pin "P$1") (pinfunction "1_P$1") (pintype "passive"))
      (node (ref "U$6") (pin "P$1") (pinfunction "1_P$1") (pintype "passive"))
      (node (ref "U$7") (pin "P$1") (pinfunction "1_P$1") (pintype "passive"))
    )
    (net (code "73") (name "unconnected-(FTDI-4-PadVCC)") (class "Default")
      (node (ref "FTDI") (pin "VCC") (pinfunction "4_VCC") (pintype "passive"))
    )
    (net (code "74") (name "unconnected-(FTDI-5-PadCTS)") (class "Default")
      (node (ref "FTDI") (pin "CTS") (pinfunction "5_CTS") (pintype "passive"))
    )
    (net (code "75") (name "unconnected-(FTDI_(SERIAL_ONLY)-1-PadDTR)") (class "Default")
      (node (ref "FTDI_(SERIAL_ONLY)") (pin "DTR") (pinfunction "1_DTR") (pintype "passive"))
    )
    (net (code "76") (name "unconnected-(FTDI_(SERIAL_ONLY)-4-PadVCC)") (class "Default")
      (node (ref "FTDI_(SERIAL_ONLY)") (pin "VCC") (pinfunction "4_VCC") (pintype "passive"))
    )
    (net (code "77") (name "unconnected-(FTDI_(SERIAL_ONLY)-5-PadCTS)") (class "Default")
      (node (ref "FTDI_(SERIAL_ONLY)") (pin "CTS") (pinfunction "5_CTS") (pintype "passive"))
    )
    (net (code "78") (name "unconnected-(J2-Pad2)") (class "Default")
      (node (ref "J2") (pin "2") (pinfunction "2_2") (pintype "passive"))
    )
    (net (code "79") (name "unconnected-(U$1-P$1_RES-PadP$1)") (class "Default")
      (node (ref "U$1") (pin "P$1") (pinfunction "P$1_RES_P$1") (pintype "bidirectional"))
    )
    (net (code "80") (name "unconnected-(U$1-P$10_DEN_G-PadP$10)") (class "Default")
      (node (ref "U$1") (pin "P$10") (pinfunction "P$10_DEN_G_P$10") (pintype "bidirectional"))
    )
    (net (code "81") (name "unconnected-(U$1-P$11_INT_G-PadP$11)") (class "Default")
      (node (ref "U$1") (pin "P$11") (pinfunction "P$11_INT_G_P$11") (pintype "bidirectional"))
    )
    (net (code "82") (name "unconnected-(U$1-P$12_DADY_G-PadP$12)") (class "Default")
      (node (ref "U$1") (pin "P$12") (pinfunction "P$12_DADY_G_P$12") (pintype "bidirectional"))
    )
    (net (code "83") (name "unconnected-(U$1-P$13_INT1_XM-PadP$13)") (class "Default")
      (node (ref "U$1") (pin "P$13") (pinfunction "P$13_INT1_XM_P$13") (pintype "bidirectional"))
    )
    (net (code "84") (name "unconnected-(U$1-P$14_INT2_XM-PadP$14)") (class "Default")
      (node (ref "U$1") (pin "P$14") (pinfunction "P$14_INT2_XM_P$14") (pintype "bidirectional"))
    )
    (net (code "85") (name "unconnected-(U2-PG3(TOSC2)-Pad17)") (class "Default")
      (node (ref "U2") (pin "17") (pinfunction "PG3(TOSC2)_17") (pintype "bidirectional"))
    )
    (net (code "86") (name "unconnected-(U2-PG4(TOSC1)-Pad18)") (class "Default")
      (node (ref "U2") (pin "18") (pinfunction "PG4(TOSC1)_18") (pintype "bidirectional"))
    )
  )
)
